# pan_schematic.net
KiCad netlist of a schematic drawn in EAGLE
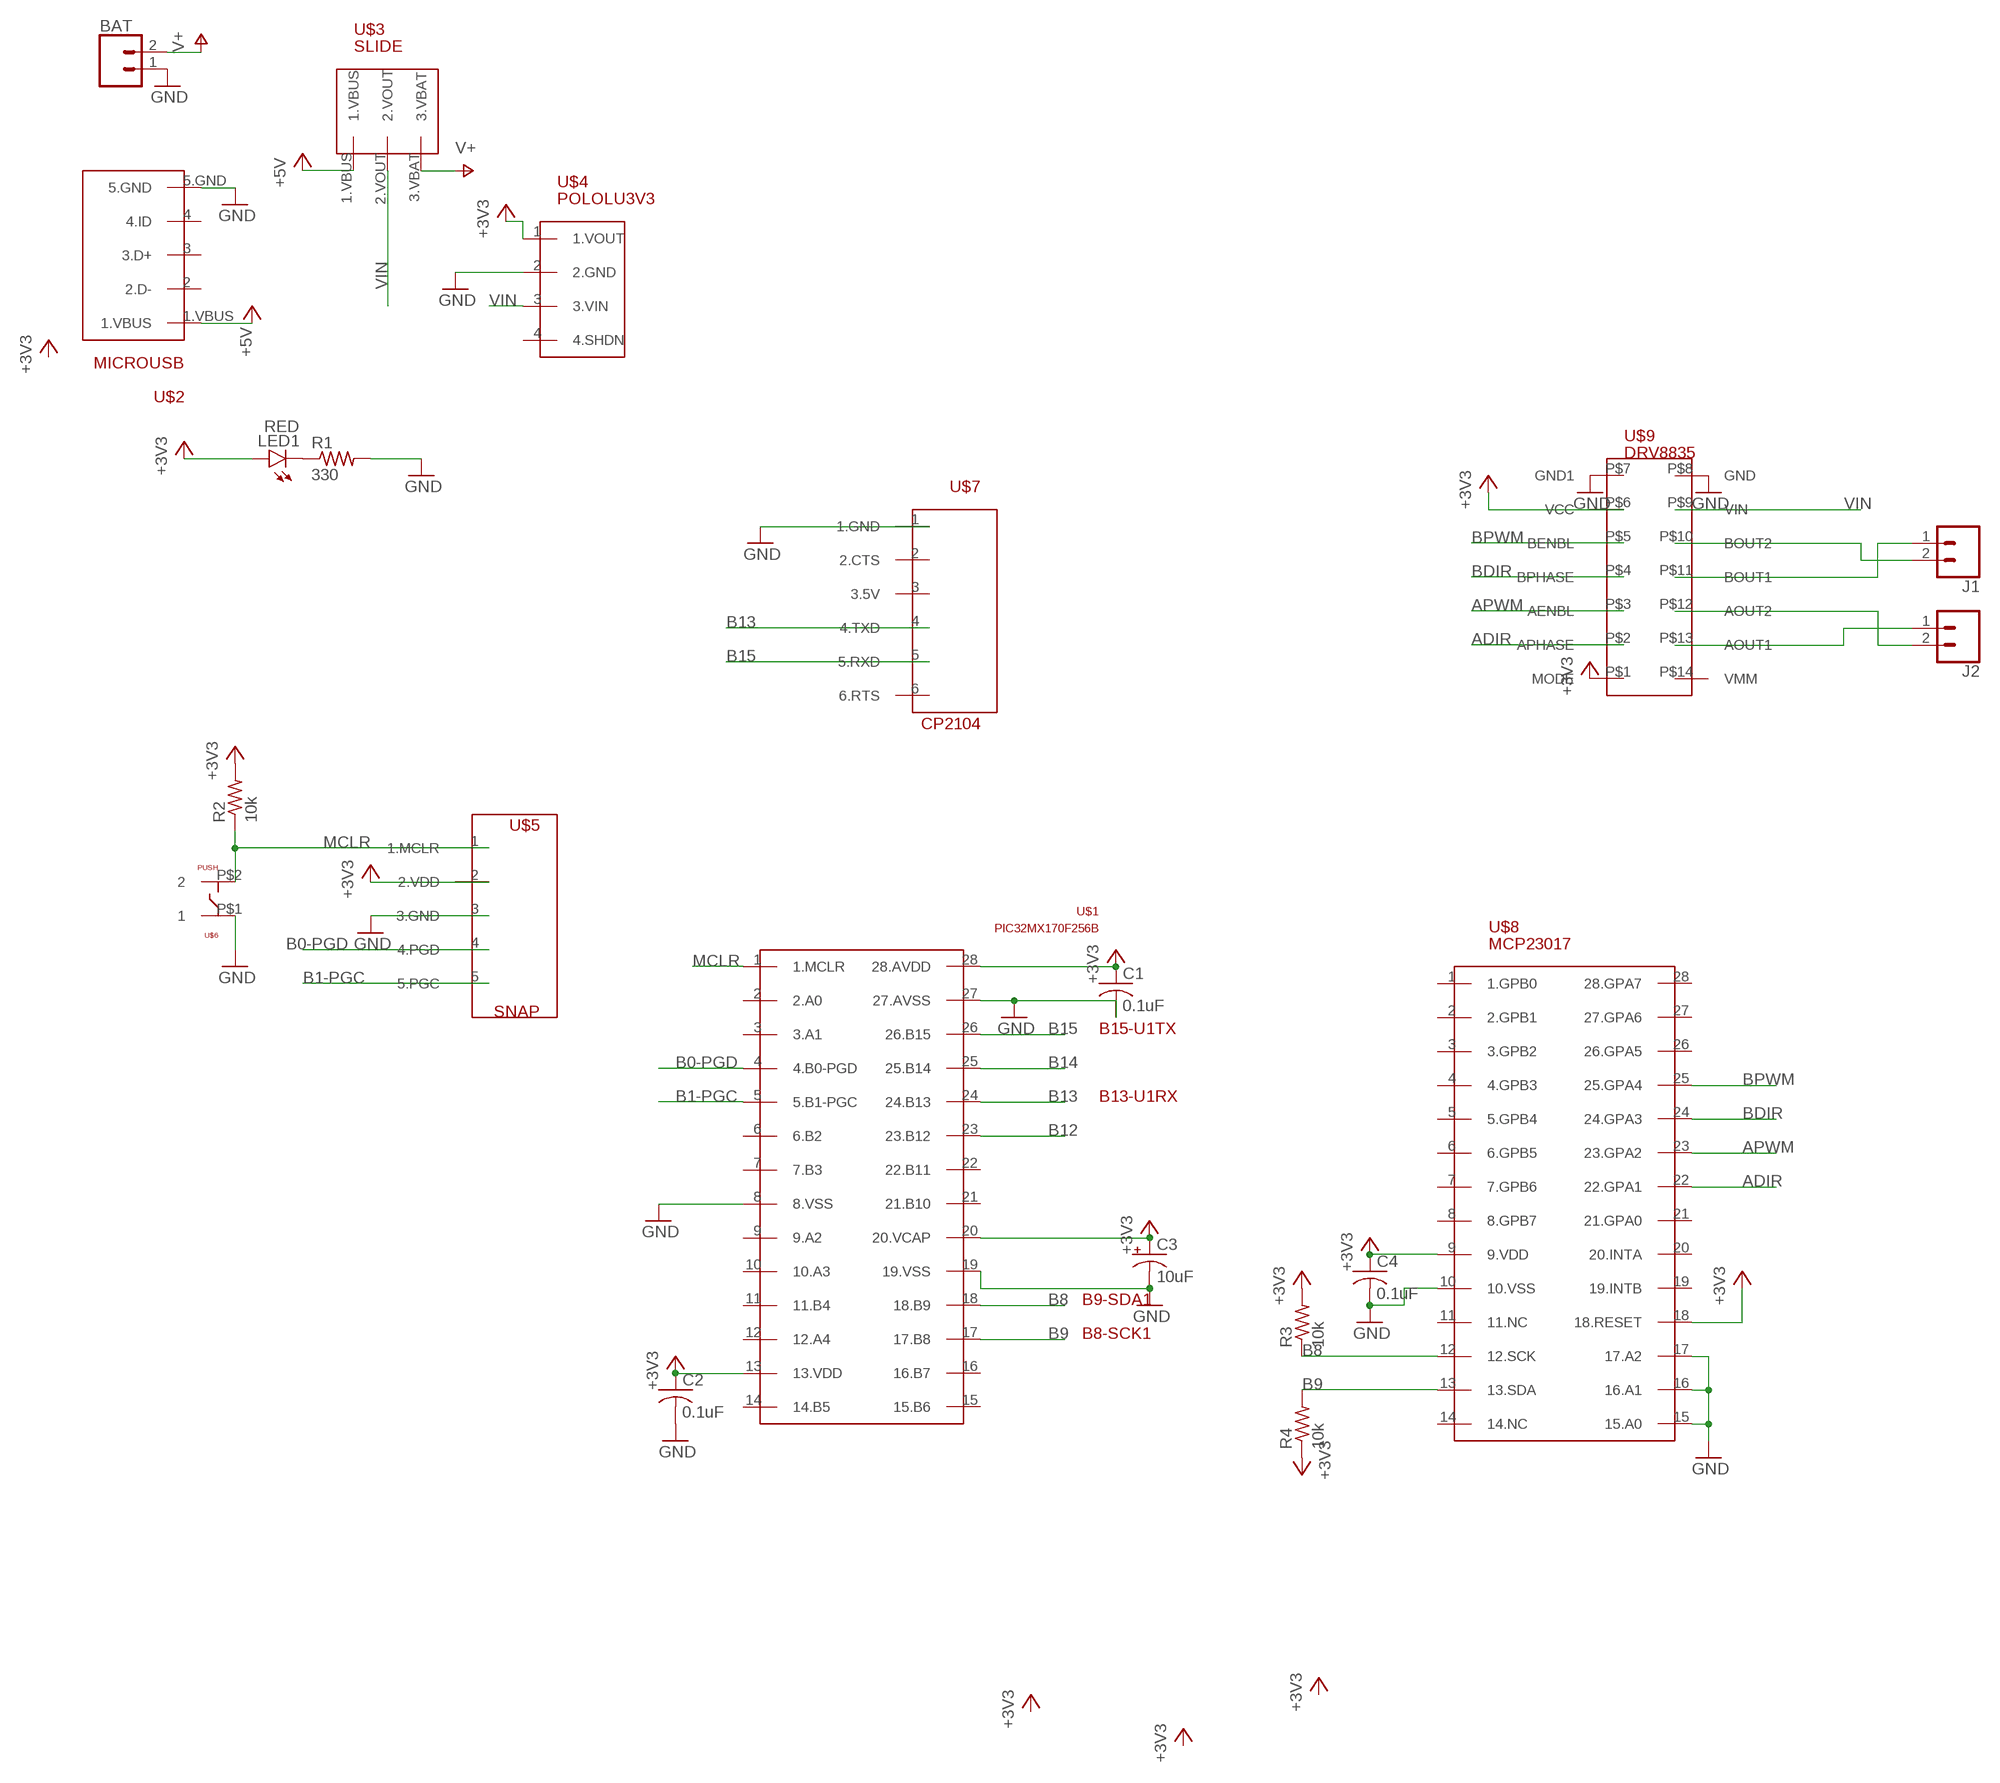
[diagram p0: schematic, sheet 1]

(export (version "E")
  (design (tool "Eeschema 10.0.6"))
  (components
    (comp (ref "BAT")
      (value "CONN_02")
      (footprint "eagle-import:1X02")
      (libsource (lib "eagle-import") (part "CONN_02"))
    )
    (comp (ref "C1")
      (value "0.1uF")
      (footprint "eagle-import:C025-030X050")
      (libsource (lib "eagle-import") (part "C-US025-030X050"))
    )
    (comp (ref "C2")
      (value "0.1uF")
      (footprint "eagle-import:C025-030X050")
      (libsource (lib "eagle-import") (part "C-US025-030X050"))
    )
    (comp (ref "C3")
      (value "10uF")
      (footprint "eagle-import:B45181B")
      (libsource (lib "eagle-import") (part "CPOL-USB45181B"))
    )
    (comp (ref "C4")
      (value "0.1uF")
      (footprint "eagle-import:C025-030X050")
      (libsource (lib "eagle-import") (part "C-US025-030X050"))
    )
    (comp (ref "J1")
      (value "CONN_02POLAR")
      (footprint "eagle-import:MOLEX-1X2")
      (libsource (lib "eagle-import") (part "CONN_02POLAR"))
    )
    (comp (ref "J2")
      (value "CONN_02POLAR")
      (footprint "eagle-import:MOLEX-1X2")
      (libsource (lib "eagle-import") (part "CONN_02POLAR"))
    )
    (comp (ref "LED1")
      (value "RED")
      (footprint "eagle-import:LED3MM")
      (libsource (lib "eagle-import") (part "LED3MM"))
    )
    (comp (ref "R1")
      (value "330")
      (footprint "eagle-import:0207_10")
      (libsource (lib "eagle-import") (part "R-US_0207/10"))
    )
    (comp (ref "R2")
      (value "10k")
      (footprint "eagle-import:0207_10")
      (libsource (lib "eagle-import") (part "R-US_0207/10"))
    )
    (comp (ref "R3")
      (value "10k")
      (footprint "eagle-import:M2012")
      (libsource (lib "eagle-import") (part "R-US_M2012"))
    )
    (comp (ref "R4")
      (value "10k")
      (footprint "eagle-import:M2012")
      (libsource (lib "eagle-import") (part "R-US_M2012"))
    )
    (comp (ref "U$1")
      (value "PIC32MX170F256B")
      (footprint "eagle-import:DIL28-3")
      (libsource (lib "eagle-import") (part "PIC32MX170F256B"))
    )
    (comp (ref "U$2")
      (value "MICROUSB")
      (footprint "eagle-import:MICROUSB")
      (libsource (lib "eagle-import") (part "MICROUSB"))
    )
    (comp (ref "U$3")
      (value "SLIDE")
      (footprint "eagle-import:SLIDE")
      (libsource (lib "eagle-import") (part "SLIDE"))
    )
    (comp (ref "U$4")
      (value "POLOLU3V3")
      (footprint "eagle-import:POLOLU3V3")
      (libsource (lib "eagle-import") (part "POLOLU3V3"))
    )
    (comp (ref "U$5")
      (value "SNAP")
      (footprint "eagle-import:1X05_1.27MM")
      (libsource (lib "eagle-import") (part "SNAP"))
    )
    (comp (ref "U$6")
      (value "PUSH")
      (footprint "eagle-import:PUSH")
      (libsource (lib "eagle-import") (part "PUSH"))
    )
    (comp (ref "U$7")
      (value "CP2104")
      (footprint "eagle-import:1X06")
      (libsource (lib "eagle-import") (part "CP2104"))
    )
    (comp (ref "U$8")
      (value "MCP23017")
      (footprint "eagle-import:MCP23017")
      (libsource (lib "eagle-import") (part "MCP23017"))
    )
    (comp (ref "U$9")
      (value "DRV8835")
      (footprint "eagle-import:DRV8835")
      (libsource (lib "eagle-import") (part "DRV8835"))
    )
  )
  (nets
    (net (code "1") (name "+3V3") (class "Default")
      (node (ref "C1") (pin "1") (pinfunction "1_1") (pintype "passive"))
      (node (ref "C2") (pin "1") (pinfunction "1_1") (pintype "passive"))
      (node (ref "C3") (pin "+") (pinfunction "+_+") (pintype "passive"))
      (node (ref "C4") (pin "1") (pinfunction "1_1") (pintype "passive"))
      (node (ref "LED1") (pin "A") (pinfunction "A_A") (pintype "passive"))
      (node (ref "R2") (pin "2") (pinfunction "2_2") (pintype "passive"))
      (node (ref "R3") (pin "2") (pinfunction "2_2") (pintype "passive"))
      (node (ref "R4") (pin "1") (pinfunction "1_1") (pintype "passive"))
      (node (ref "U$1") (pin "13") (pinfunction "13.VDD_13") (pintype "bidirectional"))
      (node (ref "U$1") (pin "20") (pinfunction "20.VCAP_20") (pintype "bidirectional"))
      (node (ref "U$1") (pin "28") (pinfunction "28.AVDD_28") (pintype "bidirectional"))
      (node (ref "U$4") (pin "1") (pinfunction "1.VOUT_1") (pintype "bidirectional"))
      (node (ref "U$5") (pin "2") (pinfunction "2.VDD_2") (pintype "bidirectional"))
      (node (ref "U$8") (pin "18") (pinfunction "18.RESET_18") (pintype "bidirectional"))
      (node (ref "U$8") (pin "9") (pinfunction "9.VDD_9") (pintype "bidirectional"))
      (node (ref "U$9") (pin "P$6") (pinfunction "VCC_P$6") (pintype "bidirectional"))
    )
    (net (code "2") (name "+5V") (class "Default")
      (node (ref "U$2") (pin "1.VBUS") (pinfunction "1.VBUS_1.VBUS") (pintype "bidirectional"))
      (node (ref "U$3") (pin "1.VBUS") (pinfunction "1.VBUS_1.VBUS") (pintype "bidirectional"))
    )
    (net (code "3") (name "/ADIR") (class "Default")
      (node (ref "U$8") (pin "22") (pinfunction "22.GPA1_22") (pintype "bidirectional"))
      (node (ref "U$9") (pin "P$2") (pinfunction "APHASE_P$2") (pintype "bidirectional"))
    )
    (net (code "4") (name "/APWM") (class "Default")
      (node (ref "U$8") (pin "23") (pinfunction "23.GPA2_23") (pintype "bidirectional"))
      (node (ref "U$9") (pin "P$3") (pinfunction "AENBL_P$3") (pintype "bidirectional"))
    )
    (net (code "5") (name "/B0-PGD") (class "Default")
      (node (ref "U$1") (pin "4") (pinfunction "4.B0-PGD_4") (pintype "bidirectional"))
      (node (ref "U$5") (pin "4") (pinfunction "4.PGD_4") (pintype "bidirectional"))
    )
    (net (code "6") (name "/B1-PGC") (class "Default")
      (node (ref "U$1") (pin "5") (pinfunction "5.B1-PGC_5") (pintype "bidirectional"))
      (node (ref "U$5") (pin "5") (pinfunction "5.PGC_5") (pintype "bidirectional"))
    )
    (net (code "7") (name "/B8") (class "Default")
      (node (ref "R3") (pin "1") (pinfunction "1_1") (pintype "passive"))
      (node (ref "U$1") (pin "18") (pinfunction "18.B9_18") (pintype "bidirectional"))
      (node (ref "U$8") (pin "12") (pinfunction "12.SCK_12") (pintype "bidirectional"))
    )
    (net (code "8") (name "/B9") (class "Default")
      (node (ref "R4") (pin "2") (pinfunction "2_2") (pintype "passive"))
      (node (ref "U$1") (pin "17") (pinfunction "17.B8_17") (pintype "bidirectional"))
      (node (ref "U$8") (pin "13") (pinfunction "13.SDA_13") (pintype "bidirectional"))
    )
    (net (code "9") (name "/B12") (class "Default")
      (node (ref "U$1") (pin "23") (pinfunction "23.B12_23") (pintype "bidirectional"))
    )
    (net (code "10") (name "/B13") (class "Default")
      (node (ref "U$1") (pin "24") (pinfunction "24.B13_24") (pintype "bidirectional"))
      (node (ref "U$7") (pin "4") (pinfunction "4.TXD_4") (pintype "bidirectional"))
    )
    (net (code "11") (name "/B14") (class "Default")
      (node (ref "U$1") (pin "25") (pinfunction "25.B14_25") (pintype "bidirectional"))
    )
    (net (code "12") (name "/B15") (class "Default")
      (node (ref "U$1") (pin "26") (pinfunction "26.B15_26") (pintype "bidirectional"))
      (node (ref "U$7") (pin "5") (pinfunction "5.RXD_5") (pintype "bidirectional"))
    )
    (net (code "13") (name "/BDIR") (class "Default")
      (node (ref "U$8") (pin "24") (pinfunction "24.GPA3_24") (pintype "bidirectional"))
      (node (ref "U$9") (pin "P$4") (pinfunction "BPHASE_P$4") (pintype "bidirectional"))
    )
    (net (code "14") (name "/BPWM") (class "Default")
      (node (ref "U$8") (pin "25") (pinfunction "25.GPA4_25") (pintype "bidirectional"))
      (node (ref "U$9") (pin "P$5") (pinfunction "BENBL_P$5") (pintype "bidirectional"))
    )
    (net (code "15") (name "/MCLR") (class "Default")
      (node (ref "R2") (pin "1") (pinfunction "1_1") (pintype "passive"))
      (node (ref "U$1") (pin "1") (pinfunction "1.MCLR_1") (pintype "bidirectional"))
      (node (ref "U$5") (pin "1") (pinfunction "1.MCLR_1") (pintype "bidirectional"))
      (node (ref "U$6") (pin "P$2") (pinfunction "2_P$2") (pintype "bidirectional"))
    )
    (net (code "16") (name "/VIN") (class "Default")
      (node (ref "U$3") (pin "2.VOUT") (pinfunction "2.VOUT_2.VOUT") (pintype "bidirectional"))
      (node (ref "U$4") (pin "3") (pinfunction "3.VIN_3") (pintype "bidirectional"))
      (node (ref "U$9") (pin "P$9") (pinfunction "VIN_P$9") (pintype "bidirectional"))
    )
    (net (code "17") (name "GND") (class "Default")
      (node (ref "BAT") (pin "1") (pinfunction "1_1") (pintype "passive"))
      (node (ref "C1") (pin "2") (pinfunction "2_2") (pintype "passive"))
      (node (ref "C2") (pin "2") (pinfunction "2_2") (pintype "passive"))
      (node (ref "C3") (pin "-") (pinfunction "-_-") (pintype "passive"))
      (node (ref "C4") (pin "2") (pinfunction "2_2") (pintype "passive"))
      (node (ref "R1") (pin "2") (pinfunction "2_2") (pintype "passive"))
      (node (ref "U$1") (pin "19") (pinfunction "19.VSS_19") (pintype "bidirectional"))
      (node (ref "U$1") (pin "27") (pinfunction "27.AVSS_27") (pintype "bidirectional"))
      (node (ref "U$1") (pin "8") (pinfunction "8.VSS_8") (pintype "bidirectional"))
      (node (ref "U$2") (pin "5.GND") (pinfunction "5.GND_5.GND") (pintype "bidirectional"))
      (node (ref "U$4") (pin "2") (pinfunction "2.GND_2") (pintype "bidirectional"))
      (node (ref "U$5") (pin "3") (pinfunction "3.GND_3") (pintype "bidirectional"))
      (node (ref "U$6") (pin "P$1") (pinfunction "1_P$1") (pintype "bidirectional"))
      (node (ref "U$7") (pin "1") (pinfunction "1.GND_1") (pintype "bidirectional"))
      (node (ref "U$8") (pin "10") (pinfunction "10.VSS_10") (pintype "bidirectional"))
      (node (ref "U$8") (pin "15") (pinfunction "15.A0_15") (pintype "bidirectional"))
      (node (ref "U$8") (pin "16") (pinfunction "16.A1_16") (pintype "bidirectional"))
      (node (ref "U$8") (pin "17") (pinfunction "17.A2_17") (pintype "bidirectional"))
    )
    (net (code "18") (name "Net-(LED1-C)") (class "Default")
      (node (ref "LED1") (pin "K") (pinfunction "C_K") (pintype "passive"))
      (node (ref "R1") (pin "1") (pinfunction "1_1") (pintype "passive"))
    )
    (net (code "19") (name "Net-(U$9-AOUT1)") (class "Default")
      (node (ref "J2") (pin "1") (pinfunction "1_1") (pintype "passive"))
      (node (ref "U$9") (pin "P$13") (pinfunction "AOUT1_P$13") (pintype "bidirectional"))
    )
    (net (code "20") (name "Net-(U$9-AOUT2)") (class "Default")
      (node (ref "J2") (pin "2") (pinfunction "2_2") (pintype "passive"))
      (node (ref "U$9") (pin "P$12") (pinfunction "AOUT2_P$12") (pintype "bidirectional"))
    )
    (net (code "21") (name "Net-(U$9-BOUT1)") (class "Default")
      (node (ref "J1") (pin "1") (pinfunction "1_1") (pintype "passive"))
      (node (ref "U$9") (pin "P$11") (pinfunction "BOUT1_P$11") (pintype "bidirectional"))
    )
    (net (code "22") (name "Net-(U$9-BOUT2)") (class "Default")
      (node (ref "J1") (pin "2") (pinfunction "2_2") (pintype "passive"))
      (node (ref "U$9") (pin "P$10") (pinfunction "BOUT2_P$10") (pintype "bidirectional"))
    )
    (net (code "23") (name "V+") (class "Default")
      (node (ref "BAT") (pin "2") (pinfunction "2_2") (pintype "passive"))
      (node (ref "U$3") (pin "3.VBAT") (pinfunction "3.VBAT_3.VBAT") (pintype "bidirectional"))
    )
    (net (code "24") (name "unconnected-(U$1-2.A0-Pad2)") (class "Default")
      (node (ref "U$1") (pin "2") (pinfunction "2.A0_2") (pintype "bidirectional"))
    )
    (net (code "25") (name "unconnected-(U$1-3.A1-Pad3)") (class "Default")
      (node (ref "U$1") (pin "3") (pinfunction "3.A1_3") (pintype "bidirectional"))
    )
    (net (code "26") (name "unconnected-(U$1-6.B2-Pad6)") (class "Default")
      (node (ref "U$1") (pin "6") (pinfunction "6.B2_6") (pintype "bidirectional"))
    )
    (net (code "27") (name "unconnected-(U$1-7.B3-Pad7)") (class "Default")
      (node (ref "U$1") (pin "7") (pinfunction "7.B3_7") (pintype "bidirectional"))
    )
    (net (code "28") (name "unconnected-(U$1-9.A2-Pad9)") (class "Default")
      (node (ref "U$1") (pin "9") (pinfunction "9.A2_9") (pintype "bidirectional"))
    )
    (net (code "29") (name "unconnected-(U$1-10.A3-Pad10)") (class "Default")
      (node (ref "U$1") (pin "10") (pinfunction "10.A3_10") (pintype "bidirectional"))
    )
    (net (code "30") (name "unconnected-(U$1-11.B4-Pad11)") (class "Default")
      (node (ref "U$1") (pin "11") (pinfunction "11.B4_11") (pintype "bidirectional"))
    )
    (net (code "31") (name "unconnected-(U$1-12.A4-Pad12)") (class "Default")
      (node (ref "U$1") (pin "12") (pinfunction "12.A4_12") (pintype "bidirectional"))
    )
    (net (code "32") (name "unconnected-(U$1-14.B5-Pad14)") (class "Default")
      (node (ref "U$1") (pin "14") (pinfunction "14.B5_14") (pintype "bidirectional"))
    )
    (net (code "33") (name "unconnected-(U$1-15.B6-Pad15)") (class "Default")
      (node (ref "U$1") (pin "15") (pinfunction "15.B6_15") (pintype "bidirectional"))
    )
    (net (code "34") (name "unconnected-(U$1-16.B7-Pad16)") (class "Default")
      (node (ref "U$1") (pin "16") (pinfunction "16.B7_16") (pintype "bidirectional"))
    )
    (net (code "35") (name "unconnected-(U$1-21.B10-Pad21)") (class "Default")
      (node (ref "U$1") (pin "21") (pinfunction "21.B10_21") (pintype "bidirectional"))
    )
    (net (code "36") (name "unconnected-(U$1-22.B11-Pad22)") (class "Default")
      (node (ref "U$1") (pin "22") (pinfunction "22.B11_22") (pintype "bidirectional"))
    )
    (net (code "37") (name "unconnected-(U$2-2.D--Pad2)") (class "Default")
      (node (ref "U$2") (pin "2") (pinfunction "2.D-_2") (pintype "bidirectional"))
    )
    (net (code "38") (name "unconnected-(U$2-3.D+-Pad3)") (class "Default")
      (node (ref "U$2") (pin "3") (pinfunction "3.D+_3") (pintype "bidirectional"))
    )
    (net (code "39") (name "unconnected-(U$2-4.ID-Pad4)") (class "Default")
      (node (ref "U$2") (pin "4") (pinfunction "4.ID_4") (pintype "bidirectional"))
    )
    (net (code "40") (name "unconnected-(U$4-4.SHDN-Pad4)") (class "Default")
      (node (ref "U$4") (pin "4") (pinfunction "4.SHDN_4") (pintype "bidirectional"))
    )
    (net (code "41") (name "unconnected-(U$7-2.CTS-Pad2)") (class "Default")
      (node (ref "U$7") (pin "2") (pinfunction "2.CTS_2") (pintype "bidirectional"))
    )
    (net (code "42") (name "unconnected-(U$7-3.5V-Pad3)") (class "Default")
      (node (ref "U$7") (pin "3") (pinfunction "3.5V_3") (pintype "bidirectional"))
    )
    (net (code "43") (name "unconnected-(U$7-6.RTS-Pad6)") (class "Default")
      (node (ref "U$7") (pin "6") (pinfunction "6.RTS_6") (pintype "bidirectional"))
    )
    (net (code "44") (name "unconnected-(U$8-1.GPB0-Pad1)") (class "Default")
      (node (ref "U$8") (pin "1") (pinfunction "1.GPB0_1") (pintype "bidirectional"))
    )
    (net (code "45") (name "unconnected-(U$8-2.GPB1-Pad2)") (class "Default")
      (node (ref "U$8") (pin "2") (pinfunction "2.GPB1_2") (pintype "bidirectional"))
    )
    (net (code "46") (name "unconnected-(U$8-3.GPB2-Pad3)") (class "Default")
      (node (ref "U$8") (pin "3") (pinfunction "3.GPB2_3") (pintype "bidirectional"))
    )
    (net (code "47") (name "unconnected-(U$8-4.GPB3-Pad4)") (class "Default")
      (node (ref "U$8") (pin "4") (pinfunction "4.GPB3_4") (pintype "bidirectional"))
    )
    (net (code "48") (name "unconnected-(U$8-5.GPB4-Pad5)") (class "Default")
      (node (ref "U$8") (pin "5") (pinfunction "5.GPB4_5") (pintype "bidirectional"))
    )
    (net (code "49") (name "unconnected-(U$8-6.GPB5-Pad6)") (class "Default")
      (node (ref "U$8") (pin "6") (pinfunction "6.GPB5_6") (pintype "bidirectional"))
    )
    (net (code "50") (name "unconnected-(U$8-7.GPB6-Pad7)") (class "Default")
      (node (ref "U$8") (pin "7") (pinfunction "7.GPB6_7") (pintype "bidirectional"))
    )
    (net (code "51") (name "unconnected-(U$8-8.GPB7-Pad8)") (class "Default")
      (node (ref "U$8") (pin "8") (pinfunction "8.GPB7_8") (pintype "bidirectional"))
    )
    (net (code "52") (name "unconnected-(U$8-11.NC-Pad11)") (class "Default")
      (node (ref "U$8") (pin "11") (pinfunction "11.NC_11") (pintype "bidirectional"))
    )
    (net (code "53") (name "unconnected-(U$8-14.NC-Pad14)") (class "Default")
      (node (ref "U$8") (pin "14") (pinfunction "14.NC_14") (pintype "bidirectional"))
    )
    (net (code "54") (name "unconnected-(U$8-19.INTB-Pad19)") (class "Default")
      (node (ref "U$8") (pin "19") (pinfunction "19.INTB_19") (pintype "bidirectional"))
    )
    (net (code "55") (name "unconnected-(U$8-20.INTA-Pad20)") (class "Default")
      (node (ref "U$8") (pin "20") (pinfunction "20.INTA_20") (pintype "bidirectional"))
    )
    (net (code "56") (name "unconnected-(U$8-21.GPA0-Pad21)") (class "Default")
      (node (ref "U$8") (pin "21") (pinfunction "21.GPA0_21") (pintype "bidirectional"))
    )
    (net (code "57") (name "unconnected-(U$8-26.GPA5-Pad26)") (class "Default")
      (node (ref "U$8") (pin "26") (pinfunction "26.GPA5_26") (pintype "bidirectional"))
    )
    (net (code "58") (name "unconnected-(U$8-27.GPA6-Pad27)") (class "Default")
      (node (ref "U$8") (pin "27") (pinfunction "27.GPA6_27") (pintype "bidirectional"))
    )
    (net (code "59") (name "unconnected-(U$8-28.GPA7-Pad28)") (class "Default")
      (node (ref "U$8") (pin "28") (pinfunction "28.GPA7_28") (pintype "bidirectional"))
    )
    (net (code "60") (name "unconnected-(U$9-GND-PadP$8)") (class "Default")
      (node (ref "U$9") (pin "P$8") (pinfunction "GND_P$8") (pintype "bidirectional"))
    )
    (net (code "61") (name "unconnected-(U$9-GND1-PadP$7)") (class "Default")
      (node (ref "U$9") (pin "P$7") (pinfunction "GND1_P$7") (pintype "bidirectional"))
    )
    (net (code "62") (name "unconnected-(U$9-MODE-PadP$1)") (class "Default")
      (node (ref "U$9") (pin "P$1") (pinfunction "MODE_P$1") (pintype "bidirectional"))
    )
    (net (code "63") (name "unconnected-(U$9-VMM-PadP$14)") (class "Default")
      (node (ref "U$9") (pin "P$14") (pinfunction "VMM_P$14") (pintype "bidirectional"))
    )
  )
)
